# Macropad_txt.net
KiCad netlist of a schematic drawn in Altium Designer
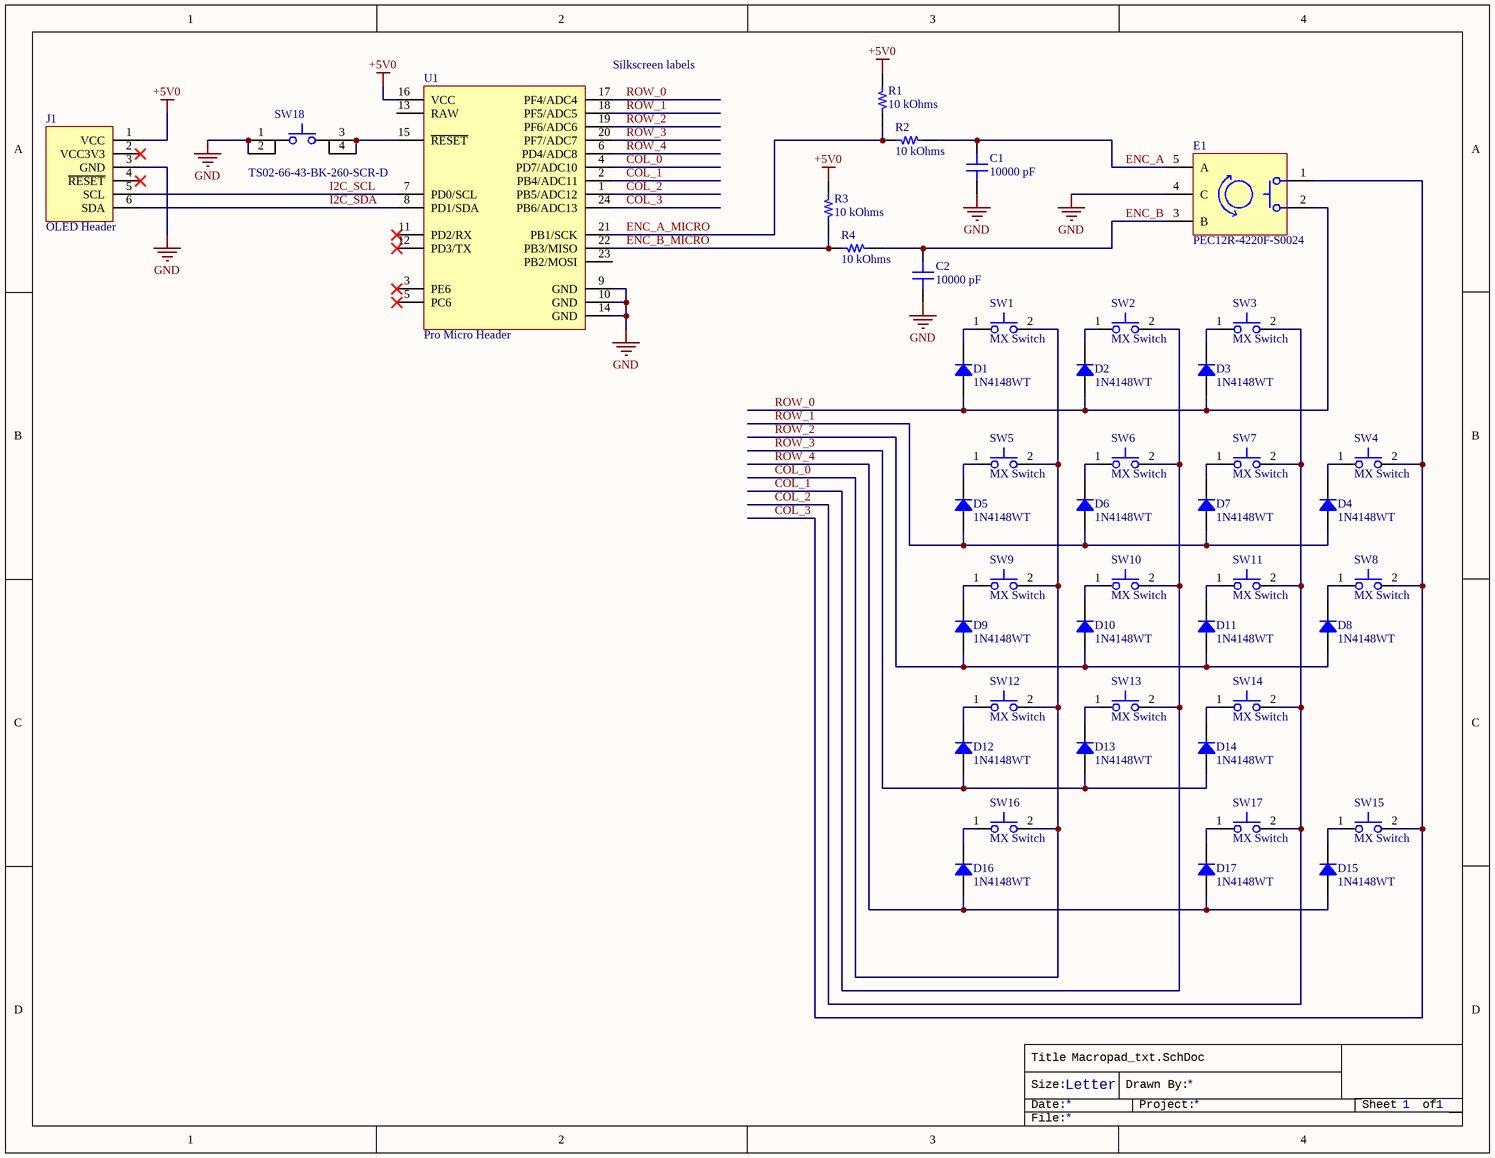
[diagram p0: Macropad_txt.SchDoc]

(export (version "E")
  (design (tool "Eeschema 10.0.6"))
  (components
    (comp (ref "C1")
      (value "10000 pF")
      (footprint "CAP 0603_1608")
      (description "CAP CER 0.01UF 250V X7R 0603")
      (fields (field (name "PART NUMBER") "C0603C103KARACAUTO") (field (name "MANUFACTURER") "KEMET"))
      (libsource (lib "Celestial Altium Library - altium_library") (part "Capacitor"))
    )
    (comp (ref "C2")
      (value "10000 pF")
      (footprint "CAP 0603_1608")
      (description "CAP CER 0.01UF 250V X7R 0603")
      (fields (field (name "PART NUMBER") "C0603C103KARACAUTO") (field (name "MANUFACTURER") "KEMET"))
      (libsource (lib "Celestial Altium Library - altium_library") (part "Capacitor"))
    )
    (comp (ref "D1")
      (value "1N4148WT")
      (footprint "SOD523F")
      (description "DIODE GEN PURP 75V 200MA SOD523F")
      (fields (field (name "MANUFACTURER") "ON Semiconductor"))
      (libsource (lib "Celestial Altium Library - altium_library") (part "Diode"))
    )
    (comp (ref "D2")
      (value "1N4148WT")
      (footprint "SOD523F")
      (description "DIODE GEN PURP 75V 200MA SOD523F")
      (fields (field (name "MANUFACTURER") "ON Semiconductor"))
      (libsource (lib "Celestial Altium Library - altium_library") (part "Diode"))
    )
    (comp (ref "D3")
      (value "1N4148WT")
      (footprint "SOD523F")
      (description "DIODE GEN PURP 75V 200MA SOD523F")
      (fields (field (name "MANUFACTURER") "ON Semiconductor"))
      (libsource (lib "Celestial Altium Library - altium_library") (part "Diode"))
    )
    (comp (ref "D4")
      (value "1N4148WT")
      (footprint "SOD523F")
      (description "DIODE GEN PURP 75V 200MA SOD523F")
      (fields (field (name "MANUFACTURER") "ON Semiconductor"))
      (libsource (lib "Celestial Altium Library - altium_library") (part "Diode"))
    )
    (comp (ref "D5")
      (value "1N4148WT")
      (footprint "SOD523F")
      (description "DIODE GEN PURP 75V 200MA SOD523F")
      (fields (field (name "MANUFACTURER") "ON Semiconductor"))
      (libsource (lib "Celestial Altium Library - altium_library") (part "Diode"))
    )
    (comp (ref "D6")
      (value "1N4148WT")
      (footprint "SOD523F")
      (description "DIODE GEN PURP 75V 200MA SOD523F")
      (fields (field (name "MANUFACTURER") "ON Semiconductor"))
      (libsource (lib "Celestial Altium Library - altium_library") (part "Diode"))
    )
    (comp (ref "D7")
      (value "1N4148WT")
      (footprint "SOD523F")
      (description "DIODE GEN PURP 75V 200MA SOD523F")
      (fields (field (name "MANUFACTURER") "ON Semiconductor"))
      (libsource (lib "Celestial Altium Library - altium_library") (part "Diode"))
    )
    (comp (ref "D8")
      (value "1N4148WT")
      (footprint "SOD523F")
      (description "DIODE GEN PURP 75V 200MA SOD523F")
      (fields (field (name "MANUFACTURER") "ON Semiconductor"))
      (libsource (lib "Celestial Altium Library - altium_library") (part "Diode"))
    )
    (comp (ref "D9")
      (value "1N4148WT")
      (footprint "SOD523F")
      (description "DIODE GEN PURP 75V 200MA SOD523F")
      (fields (field (name "MANUFACTURER") "ON Semiconductor"))
      (libsource (lib "Celestial Altium Library - altium_library") (part "Diode"))
    )
    (comp (ref "D10")
      (value "1N4148WT")
      (footprint "SOD523F")
      (description "DIODE GEN PURP 75V 200MA SOD523F")
      (fields (field (name "MANUFACTURER") "ON Semiconductor"))
      (libsource (lib "Celestial Altium Library - altium_library") (part "Diode"))
    )
    (comp (ref "D11")
      (value "1N4148WT")
      (footprint "SOD523F")
      (description "DIODE GEN PURP 75V 200MA SOD523F")
      (fields (field (name "MANUFACTURER") "ON Semiconductor"))
      (libsource (lib "Celestial Altium Library - altium_library") (part "Diode"))
    )
    (comp (ref "D12")
      (value "1N4148WT")
      (footprint "SOD523F")
      (description "DIODE GEN PURP 75V 200MA SOD523F")
      (fields (field (name "MANUFACTURER") "ON Semiconductor"))
      (libsource (lib "Celestial Altium Library - altium_library") (part "Diode"))
    )
    (comp (ref "D13")
      (value "1N4148WT")
      (footprint "SOD523F")
      (description "DIODE GEN PURP 75V 200MA SOD523F")
      (fields (field (name "MANUFACTURER") "ON Semiconductor"))
      (libsource (lib "Celestial Altium Library - altium_library") (part "Diode"))
    )
    (comp (ref "D14")
      (value "1N4148WT")
      (footprint "SOD523F")
      (description "DIODE GEN PURP 75V 200MA SOD523F")
      (fields (field (name "MANUFACTURER") "ON Semiconductor"))
      (libsource (lib "Celestial Altium Library - altium_library") (part "Diode"))
    )
    (comp (ref "D15")
      (value "1N4148WT")
      (footprint "SOD523F")
      (description "DIODE GEN PURP 75V 200MA SOD523F")
      (fields (field (name "MANUFACTURER") "ON Semiconductor"))
      (libsource (lib "Celestial Altium Library - altium_library") (part "Diode"))
    )
    (comp (ref "D16")
      (value "1N4148WT")
      (footprint "SOD523F")
      (description "DIODE GEN PURP 75V 200MA SOD523F")
      (fields (field (name "MANUFACTURER") "ON Semiconductor"))
      (libsource (lib "Celestial Altium Library - altium_library") (part "Diode"))
    )
    (comp (ref "D17")
      (value "1N4148WT")
      (footprint "SOD523F")
      (description "DIODE GEN PURP 75V 200MA SOD523F")
      (fields (field (name "MANUFACTURER") "ON Semiconductor"))
      (libsource (lib "Celestial Altium Library - altium_library") (part "Diode"))
    )
    (comp (ref "E1") (value "PEC12R-4220F-S0024") (libsource (lib "Macropad") (part "PEC12R-4220F-S0024")))
    (comp (ref "J1") (value "OLED Header") (libsource (lib "Macropad") (part "OLED Header")))
    (comp (ref "R1")
      (value "10 kOhms")
      (footprint "RES 0603_1608")
      (description "RES SMD 10K OHM 0.1% 1/8W 0603")
      (fields
        (field (name "PART NUMBER") "MCT0603MD1002BP100")
        (field (name "MANUFACTURER") "Vishay Beyschlag")
      )
      (libsource (lib "Celestial Altium Library - altium_library") (part "Resistor"))
    )
    (comp (ref "R2")
      (value "10 kOhms")
      (footprint "RES 0603_1608")
      (description "RES SMD 10K OHM 0.1% 1/8W 0603")
      (fields
        (field (name "PART NUMBER") "MCT0603MD1002BP100")
        (field (name "MANUFACTURER") "Vishay Beyschlag")
      )
      (libsource (lib "Celestial Altium Library - altium_library") (part "Resistor"))
    )
    (comp (ref "R3")
      (value "10 kOhms")
      (footprint "RES 0603_1608")
      (description "RES SMD 10K OHM 0.1% 1/8W 0603")
      (fields
        (field (name "PART NUMBER") "MCT0603MD1002BP100")
        (field (name "MANUFACTURER") "Vishay Beyschlag")
      )
      (libsource (lib "Celestial Altium Library - altium_library") (part "Resistor"))
    )
    (comp (ref "R4")
      (value "10 kOhms")
      (footprint "RES 0603_1608")
      (description "RES SMD 10K OHM 0.1% 1/8W 0603")
      (fields
        (field (name "PART NUMBER") "MCT0603MD1002BP100")
        (field (name "MANUFACTURER") "Vishay Beyschlag")
      )
      (libsource (lib "Celestial Altium Library - altium_library") (part "Resistor"))
    )
    (comp (ref "SW1")
      (value "MX Switch")
      (footprint "MXSwitch")
      (libsource (lib "Macropad") (part "MX Switch"))
    )
    (comp (ref "SW2")
      (value "MX Switch")
      (footprint "MXSwitch")
      (libsource (lib "Macropad") (part "MX Switch"))
    )
    (comp (ref "SW3")
      (value "MX Switch")
      (footprint "MXSwitch")
      (libsource (lib "Macropad") (part "MX Switch"))
    )
    (comp (ref "SW4")
      (value "MX Switch")
      (footprint "MXSwitch")
      (libsource (lib "Macropad") (part "MX Switch"))
    )
    (comp (ref "SW5")
      (value "MX Switch")
      (footprint "MXSwitch")
      (libsource (lib "Macropad") (part "MX Switch"))
    )
    (comp (ref "SW6")
      (value "MX Switch")
      (footprint "MXSwitch")
      (libsource (lib "Macropad") (part "MX Switch"))
    )
    (comp (ref "SW7")
      (value "MX Switch")
      (footprint "MXSwitch")
      (libsource (lib "Macropad") (part "MX Switch"))
    )
    (comp (ref "SW8")
      (value "MX Switch")
      (footprint "MXSwitch")
      (libsource (lib "Macropad") (part "MX Switch"))
    )
    (comp (ref "SW9")
      (value "MX Switch")
      (footprint "MXSwitch")
      (libsource (lib "Macropad") (part "MX Switch"))
    )
    (comp (ref "SW10")
      (value "MX Switch")
      (footprint "MXSwitch")
      (libsource (lib "Macropad") (part "MX Switch"))
    )
    (comp (ref "SW11")
      (value "MX Switch")
      (footprint "MXSwitch")
      (libsource (lib "Macropad") (part "MX Switch"))
    )
    (comp (ref "SW12")
      (value "MX Switch")
      (footprint "MXSwitch")
      (libsource (lib "Macropad") (part "MX Switch"))
    )
    (comp (ref "SW13")
      (value "MX Switch")
      (footprint "MXSwitch")
      (libsource (lib "Macropad") (part "MX Switch"))
    )
    (comp (ref "SW14")
      (value "MX Switch")
      (footprint "MXSwitch")
      (libsource (lib "Macropad") (part "MX Switch"))
    )
    (comp (ref "SW15")
      (value "MX Switch")
      (footprint "MXSwitch")
      (libsource (lib "Macropad") (part "MX Switch"))
    )
    (comp (ref "SW16")
      (value "MX Switch")
      (footprint "MXSwitch")
      (libsource (lib "Macropad") (part "MX Switch"))
    )
    (comp (ref "SW17")
      (value "MX Switch")
      (footprint "MXSwitch")
      (libsource (lib "Macropad") (part "MX Switch"))
    )
    (comp (ref "SW18")
      (value "TS02-66-43-BK-260-SCR-D")
      (footprint "TS02-66-43-BK-260-SCR-D")
      (libsource (lib "Macropad") (part "TS02-66-43-BK-260-SCR-D"))
    )
    (comp (ref "U1")
      (value "Pro Micro Header")
      (description "Pro Micro")
      (libsource (lib "Macropad") (part "DEV-12640"))
    )
  )
  (nets
    (net (code "1") (name "+5V0") (class "Default")
      (node (ref "J1") (pin "1") (pinfunction "VCC_1") (pintype "passive"))
      (node (ref "R1") (pin "1") (pinfunction "1_1") (pintype "passive"))
      (node (ref "R3") (pin "1") (pinfunction "1_1") (pintype "passive"))
      (node (ref "U1") (pin "16") (pinfunction "VCC_16") (pintype "passive"))
    )
    (net (code "2") (name "/COL_0") (class "Default")
      (node (ref "SW1") (pin "2") (pinfunction "2_2") (pintype "passive"))
      (node (ref "SW12") (pin "2") (pinfunction "2_2") (pintype "passive"))
      (node (ref "SW16") (pin "2") (pinfunction "2_2") (pintype "passive"))
      (node (ref "SW5") (pin "2") (pinfunction "2_2") (pintype "passive"))
      (node (ref "SW9") (pin "2") (pinfunction "2_2") (pintype "passive"))
      (node (ref "U1") (pin "4") (pinfunction "PD7/ADC10_4") (pintype "passive"))
    )
    (net (code "3") (name "/COL_1") (class "Default")
      (node (ref "SW10") (pin "2") (pinfunction "2_2") (pintype "passive"))
      (node (ref "SW13") (pin "2") (pinfunction "2_2") (pintype "passive"))
      (node (ref "SW2") (pin "2") (pinfunction "2_2") (pintype "passive"))
      (node (ref "SW6") (pin "2") (pinfunction "2_2") (pintype "passive"))
      (node (ref "U1") (pin "2") (pinfunction "PB4/ADC11_2") (pintype "passive"))
    )
    (net (code "4") (name "/COL_2") (class "Default")
      (node (ref "SW11") (pin "2") (pinfunction "2_2") (pintype "passive"))
      (node (ref "SW14") (pin "2") (pinfunction "2_2") (pintype "passive"))
      (node (ref "SW17") (pin "2") (pinfunction "2_2") (pintype "passive"))
      (node (ref "SW3") (pin "2") (pinfunction "2_2") (pintype "passive"))
      (node (ref "SW7") (pin "2") (pinfunction "2_2") (pintype "passive"))
      (node (ref "U1") (pin "1") (pinfunction "PB5/ADC12_1") (pintype "passive"))
    )
    (net (code "5") (name "/COL_3") (class "Default")
      (node (ref "E1") (pin "1") (pinfunction "1_1") (pintype "passive"))
      (node (ref "SW15") (pin "2") (pinfunction "2_2") (pintype "passive"))
      (node (ref "SW4") (pin "2") (pinfunction "2_2") (pintype "passive"))
      (node (ref "SW8") (pin "2") (pinfunction "2_2") (pintype "passive"))
      (node (ref "U1") (pin "24") (pinfunction "PB6/ADC13_24") (pintype "passive"))
    )
    (net (code "6") (name "/ENC_A") (class "Default")
      (node (ref "C1") (pin "2") (pinfunction "2_2") (pintype "passive"))
      (node (ref "E1") (pin "5") (pinfunction "A_5") (pintype "passive"))
      (node (ref "R2") (pin "1") (pinfunction "1_1") (pintype "passive"))
    )
    (net (code "7") (name "/ENC_A_MICRO") (class "Default")
      (node (ref "R1") (pin "2") (pinfunction "2_2") (pintype "passive"))
      (node (ref "R2") (pin "2") (pinfunction "2_2") (pintype "passive"))
      (node (ref "U1") (pin "21") (pinfunction "PB1/SCK_21") (pintype "passive"))
    )
    (net (code "8") (name "/ENC_B") (class "Default")
      (node (ref "C2") (pin "2") (pinfunction "2_2") (pintype "passive"))
      (node (ref "E1") (pin "3") (pinfunction "B_3") (pintype "passive"))
      (node (ref "R4") (pin "1") (pinfunction "1_1") (pintype "passive"))
    )
    (net (code "9") (name "/ENC_B_MICRO") (class "Default")
      (node (ref "R3") (pin "2") (pinfunction "2_2") (pintype "passive"))
      (node (ref "R4") (pin "2") (pinfunction "2_2") (pintype "passive"))
      (node (ref "U1") (pin "22") (pinfunction "PB3/MISO_22") (pintype "passive"))
    )
    (net (code "10") (name "/I2C_SCL") (class "Default")
      (node (ref "J1") (pin "5") (pinfunction "SCL_5") (pintype "passive"))
      (node (ref "U1") (pin "7") (pinfunction "PD0/SCL_7") (pintype "passive"))
    )
    (net (code "11") (name "/I2C_SDA") (class "Default")
      (node (ref "J1") (pin "6") (pinfunction "SDA_6") (pintype "passive"))
      (node (ref "U1") (pin "8") (pinfunction "PD1/SDA_8") (pintype "passive"))
    )
    (net (code "12") (name "/ROW_0") (class "Default")
      (node (ref "D1") (pin "1") (pinfunction "1_1") (pintype "passive"))
      (node (ref "D2") (pin "1") (pinfunction "1_1") (pintype "passive"))
      (node (ref "D3") (pin "1") (pinfunction "1_1") (pintype "passive"))
      (node (ref "E1") (pin "2") (pinfunction "2_2") (pintype "passive"))
      (node (ref "U1") (pin "17") (pinfunction "PF4/ADC4_17") (pintype "passive"))
    )
    (net (code "13") (name "/ROW_1") (class "Default")
      (node (ref "D4") (pin "1") (pinfunction "1_1") (pintype "passive"))
      (node (ref "D5") (pin "1") (pinfunction "1_1") (pintype "passive"))
      (node (ref "D6") (pin "1") (pinfunction "1_1") (pintype "passive"))
      (node (ref "D7") (pin "1") (pinfunction "1_1") (pintype "passive"))
      (node (ref "U1") (pin "18") (pinfunction "PF5/ADC5_18") (pintype "passive"))
    )
    (net (code "14") (name "/ROW_2") (class "Default")
      (node (ref "D10") (pin "1") (pinfunction "1_1") (pintype "passive"))
      (node (ref "D11") (pin "1") (pinfunction "1_1") (pintype "passive"))
      (node (ref "D8") (pin "1") (pinfunction "1_1") (pintype "passive"))
      (node (ref "D9") (pin "1") (pinfunction "1_1") (pintype "passive"))
      (node (ref "U1") (pin "19") (pinfunction "PF6/ADC6_19") (pintype "passive"))
    )
    (net (code "15") (name "/ROW_3") (class "Default")
      (node (ref "D12") (pin "1") (pinfunction "1_1") (pintype "passive"))
      (node (ref "D13") (pin "1") (pinfunction "1_1") (pintype "passive"))
      (node (ref "D14") (pin "1") (pinfunction "1_1") (pintype "passive"))
      (node (ref "U1") (pin "20") (pinfunction "PF7/ADC7_20") (pintype "passive"))
    )
    (net (code "16") (name "/ROW_4") (class "Default")
      (node (ref "D15") (pin "1") (pinfunction "1_1") (pintype "passive"))
      (node (ref "D16") (pin "1") (pinfunction "1_1") (pintype "passive"))
      (node (ref "D17") (pin "1") (pinfunction "1_1") (pintype "passive"))
      (node (ref "U1") (pin "6") (pinfunction "PD4/ADC8_6") (pintype "passive"))
    )
    (net (code "17") (name "GND") (class "Default")
      (node (ref "C1") (pin "1") (pinfunction "1_1") (pintype "passive"))
      (node (ref "C2") (pin "1") (pinfunction "1_1") (pintype "passive"))
      (node (ref "E1") (pin "4") (pinfunction "C_4") (pintype "passive"))
      (node (ref "J1") (pin "3") (pinfunction "GND_3") (pintype "passive"))
      (node (ref "SW18") (pin "1") (pinfunction "1_1") (pintype "passive"))
      (node (ref "SW18") (pin "2") (pinfunction "2_2") (pintype "passive"))
      (node (ref "U1") (pin "10") (pinfunction "GND_10") (pintype "passive"))
      (node (ref "U1") (pin "14") (pinfunction "GND_14") (pintype "passive"))
      (node (ref "U1") (pin "9") (pinfunction "GND_9") (pintype "passive"))
    )
    (net (code "18") (name "Net-(D1-Pad2)") (class "Default")
      (node (ref "D1") (pin "2") (pinfunction "2_2") (pintype "passive"))
      (node (ref "SW1") (pin "1") (pinfunction "1_1") (pintype "passive"))
    )
    (net (code "19") (name "Net-(D2-Pad2)") (class "Default")
      (node (ref "D2") (pin "2") (pinfunction "2_2") (pintype "passive"))
      (node (ref "SW2") (pin "1") (pinfunction "1_1") (pintype "passive"))
    )
    (net (code "20") (name "Net-(D3-Pad2)") (class "Default")
      (node (ref "D3") (pin "2") (pinfunction "2_2") (pintype "passive"))
      (node (ref "SW3") (pin "1") (pinfunction "1_1") (pintype "passive"))
    )
    (net (code "21") (name "Net-(D4-Pad2)") (class "Default")
      (node (ref "D4") (pin "2") (pinfunction "2_2") (pintype "passive"))
      (node (ref "SW4") (pin "1") (pinfunction "1_1") (pintype "passive"))
    )
    (net (code "22") (name "Net-(D5-Pad2)") (class "Default")
      (node (ref "D5") (pin "2") (pinfunction "2_2") (pintype "passive"))
      (node (ref "SW5") (pin "1") (pinfunction "1_1") (pintype "passive"))
    )
    (net (code "23") (name "Net-(D6-Pad2)") (class "Default")
      (node (ref "D6") (pin "2") (pinfunction "2_2") (pintype "passive"))
      (node (ref "SW6") (pin "1") (pinfunction "1_1") (pintype "passive"))
    )
    (net (code "24") (name "Net-(D7-Pad2)") (class "Default")
      (node (ref "D7") (pin "2") (pinfunction "2_2") (pintype "passive"))
      (node (ref "SW7") (pin "1") (pinfunction "1_1") (pintype "passive"))
    )
    (net (code "25") (name "Net-(D8-Pad2)") (class "Default")
      (node (ref "D8") (pin "2") (pinfunction "2_2") (pintype "passive"))
      (node (ref "SW8") (pin "1") (pinfunction "1_1") (pintype "passive"))
    )
    (net (code "26") (name "Net-(D9-Pad2)") (class "Default")
      (node (ref "D9") (pin "2") (pinfunction "2_2") (pintype "passive"))
      (node (ref "SW9") (pin "1") (pinfunction "1_1") (pintype "passive"))
    )
    (net (code "27") (name "Net-(D10-Pad2)") (class "Default")
      (node (ref "D10") (pin "2") (pinfunction "2_2") (pintype "passive"))
      (node (ref "SW10") (pin "1") (pinfunction "1_1") (pintype "passive"))
    )
    (net (code "28") (name "Net-(D11-Pad2)") (class "Default")
      (node (ref "D11") (pin "2") (pinfunction "2_2") (pintype "passive"))
      (node (ref "SW11") (pin "1") (pinfunction "1_1") (pintype "passive"))
    )
    (net (code "29") (name "Net-(D12-Pad2)") (class "Default")
      (node (ref "D12") (pin "2") (pinfunction "2_2") (pintype "passive"))
      (node (ref "SW12") (pin "1") (pinfunction "1_1") (pintype "passive"))
    )
    (net (code "30") (name "Net-(D13-Pad2)") (class "Default")
      (node (ref "D13") (pin "2") (pinfunction "2_2") (pintype "passive"))
      (node (ref "SW13") (pin "1") (pinfunction "1_1") (pintype "passive"))
    )
    (net (code "31") (name "Net-(D14-Pad2)") (class "Default")
      (node (ref "D14") (pin "2") (pinfunction "2_2") (pintype "passive"))
      (node (ref "SW14") (pin "1") (pinfunction "1_1") (pintype "passive"))
    )
    (net (code "32") (name "Net-(D15-Pad2)") (class "Default")
      (node (ref "D15") (pin "2") (pinfunction "2_2") (pintype "passive"))
      (node (ref "SW15") (pin "1") (pinfunction "1_1") (pintype "passive"))
    )
    (net (code "33") (name "Net-(D16-Pad2)") (class "Default")
      (node (ref "D16") (pin "2") (pinfunction "2_2") (pintype "passive"))
      (node (ref "SW16") (pin "1") (pinfunction "1_1") (pintype "passive"))
    )
    (net (code "34") (name "Net-(D17-Pad2)") (class "Default")
      (node (ref "D17") (pin "2") (pinfunction "2_2") (pintype "passive"))
      (node (ref "SW17") (pin "1") (pinfunction "1_1") (pintype "passive"))
    )
    (net (code "35") (name "Net-(U1-~{RESET})") (class "Default")
      (node (ref "SW18") (pin "3") (pinfunction "3_3") (pintype "passive"))
      (node (ref "SW18") (pin "4") (pinfunction "4_4") (pintype "passive"))
      (node (ref "U1") (pin "15") (pinfunction "~{RESET}_15") (pintype "passive"))
    )
    (net (code "36") (name "unconnected-(J1-VCC3V3-Pad2)") (class "Default")
      (node (ref "J1") (pin "2") (pinfunction "VCC3V3_2") (pintype "passive+no_connect"))
    )
    (net (code "37") (name "unconnected-(J1-~{RESET}-Pad4)") (class "Default")
      (node (ref "J1") (pin "4") (pinfunction "~{RESET}_4") (pintype "passive+no_connect"))
    )
    (net (code "38") (name "unconnected-(U1-PB2{slash}MOSI-Pad23)") (class "Default")
      (node (ref "U1") (pin "23") (pinfunction "PB2/MOSI_23") (pintype "passive"))
    )
    (net (code "39") (name "unconnected-(U1-PC6-Pad5)") (class "Default")
      (node (ref "U1") (pin "5") (pinfunction "PC6_5") (pintype "passive+no_connect"))
    )
    (net (code "40") (name "unconnected-(U1-PD2{slash}RX-Pad11)") (class "Default")
      (node (ref "U1") (pin "11") (pinfunction "PD2/RX_11") (pintype "passive+no_connect"))
    )
    (net (code "41") (name "unconnected-(U1-PD3{slash}TX-Pad12)") (class "Default")
      (node (ref "U1") (pin "12") (pinfunction "PD3/TX_12") (pintype "passive+no_connect"))
    )
    (net (code "42") (name "unconnected-(U1-PE6-Pad3)") (class "Default")
      (node (ref "U1") (pin "3") (pinfunction "PE6_3") (pintype "passive+no_connect"))
    )
    (net (code "43") (name "unconnected-(U1-RAW-Pad13)") (class "Default")
      (node (ref "U1") (pin "13") (pinfunction "RAW_13") (pintype "passive"))
    )
  )
)
